# lcd5v.net
KiCad netlist of a schematic drawn in Altium Designer
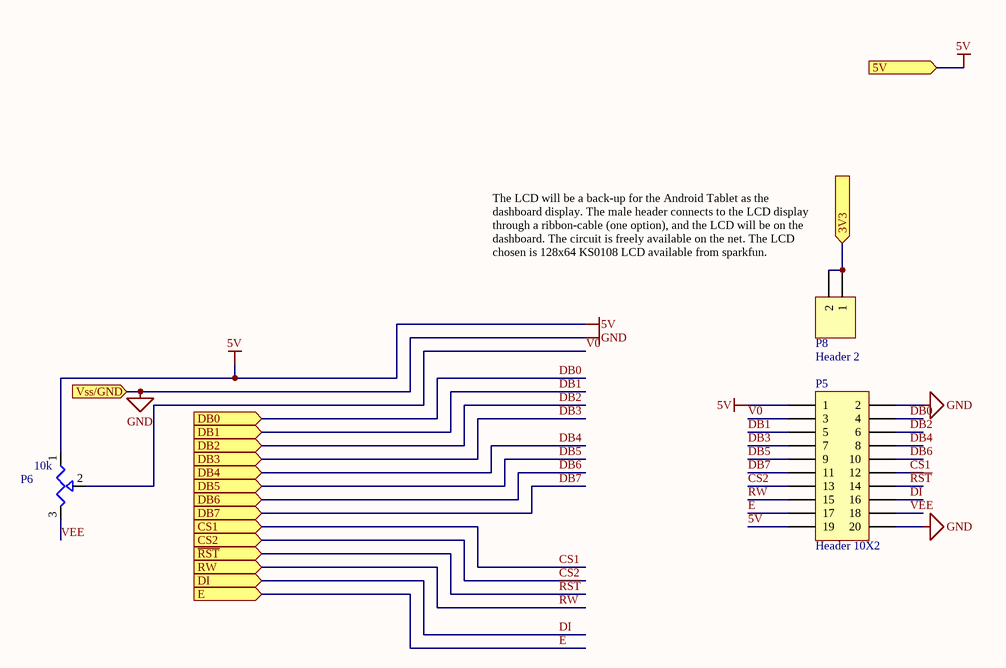
[diagram p0: lcd5v.SchDoc]

(export (version "E")
  (design (tool "Eeschema 10.0.6"))
  (components
    (comp (ref "P5")
      (value "Header 10X2")
      (footprint "HDR2X10")
      (description "Header, 10-Pin, Dual row")
      (fields (field (name "PUBLISHER") "Altium Limited"))
      (libsource (lib "Miscellaneous Connectors") (part "Header 10X2"))
    )
    (comp (ref "P6")
      (value "10k")
      (footprint "TC33")
      (description "3mm SMD Trimming Pot")
      (fields (field (name "MANUFACTURER") "Bourns") (field (name "Comment") "Trimmer"))
      (libsource (lib "add-integrated-library") (part "TC33"))
    )
    (comp (ref "P8")
      (value "Header 2")
      (footprint "HDR1X2")
      (description "Header, 2-Pin")
      (fields (field (name "PUBLISHER") "Altium Limited"))
      (libsource (lib "Miscellaneous Connectors") (part "Header 2"))
    )
  )
  (nets
    (net (code "1") (name "/3V3") (class "Default")
      (node (ref "P8") (pin "1") (pinfunction "1_1") (pintype "passive"))
      (node (ref "P8") (pin "2") (pinfunction "2_2") (pintype "passive"))
    )
    (net (code "2") (name "/CS1") (class "Default")
      (node (ref "P5") (pin "12") (pinfunction "12_12") (pintype "passive"))
    )
    (net (code "3") (name "/CS2") (class "Default")
      (node (ref "P5") (pin "13") (pinfunction "13_13") (pintype "passive"))
    )
    (net (code "4") (name "/DB0") (class "Default")
      (node (ref "P5") (pin "4") (pinfunction "4_4") (pintype "passive"))
    )
    (net (code "5") (name "/DB1") (class "Default")
      (node (ref "P5") (pin "5") (pinfunction "5_5") (pintype "passive"))
    )
    (net (code "6") (name "/DB2") (class "Default")
      (node (ref "P5") (pin "6") (pinfunction "6_6") (pintype "passive"))
    )
    (net (code "7") (name "/DB3") (class "Default")
      (node (ref "P5") (pin "7") (pinfunction "7_7") (pintype "passive"))
    )
    (net (code "8") (name "/DB4") (class "Default")
      (node (ref "P5") (pin "8") (pinfunction "8_8") (pintype "passive"))
    )
    (net (code "9") (name "/DB5") (class "Default")
      (node (ref "P5") (pin "9") (pinfunction "9_9") (pintype "passive"))
    )
    (net (code "10") (name "/DB6") (class "Default")
      (node (ref "P5") (pin "10") (pinfunction "10_10") (pintype "passive"))
    )
    (net (code "11") (name "/DB7") (class "Default")
      (node (ref "P5") (pin "11") (pinfunction "11_11") (pintype "passive"))
    )
    (net (code "12") (name "/DI") (class "Default")
      (node (ref "P5") (pin "16") (pinfunction "16_16") (pintype "passive"))
    )
    (net (code "13") (name "/E") (class "Default")
      (node (ref "P5") (pin "17") (pinfunction "17_17") (pintype "passive"))
    )
    (net (code "14") (name "/RW") (class "Default")
      (node (ref "P5") (pin "15") (pinfunction "15_15") (pintype "passive"))
    )
    (net (code "15") (name "/V0") (class "Default")
      (node (ref "P5") (pin "3") (pinfunction "3_3") (pintype "passive"))
      (node (ref "P6") (pin "2") (pinfunction "WIPER_2") (pintype "passive"))
    )
    (net (code "16") (name "/VEE") (class "Default")
      (node (ref "P5") (pin "18") (pinfunction "18_18") (pintype "passive"))
      (node (ref "P6") (pin "3") (pinfunction "CW_3") (pintype "passive"))
    )
    (net (code "17") (name "/~{RST}") (class "Default")
      (node (ref "P5") (pin "14") (pinfunction "14_14") (pintype "passive"))
    )
    (net (code "18") (name "5V") (class "Default")
      (node (ref "P5") (pin "1") (pinfunction "1_1") (pintype "passive"))
      (node (ref "P5") (pin "19") (pinfunction "19_19") (pintype "passive"))
      (node (ref "P6") (pin "1") (pinfunction "CCW_1") (pintype "passive"))
    )
    (net (code "19") (name "GND") (class "Default")
      (node (ref "P5") (pin "2") (pinfunction "2_2") (pintype "passive"))
      (node (ref "P5") (pin "20") (pinfunction "20_20") (pintype "passive"))
    )
  )
)
